# H-bro_gear.net
KiCad netlist of a schematic drawn in EAGLE
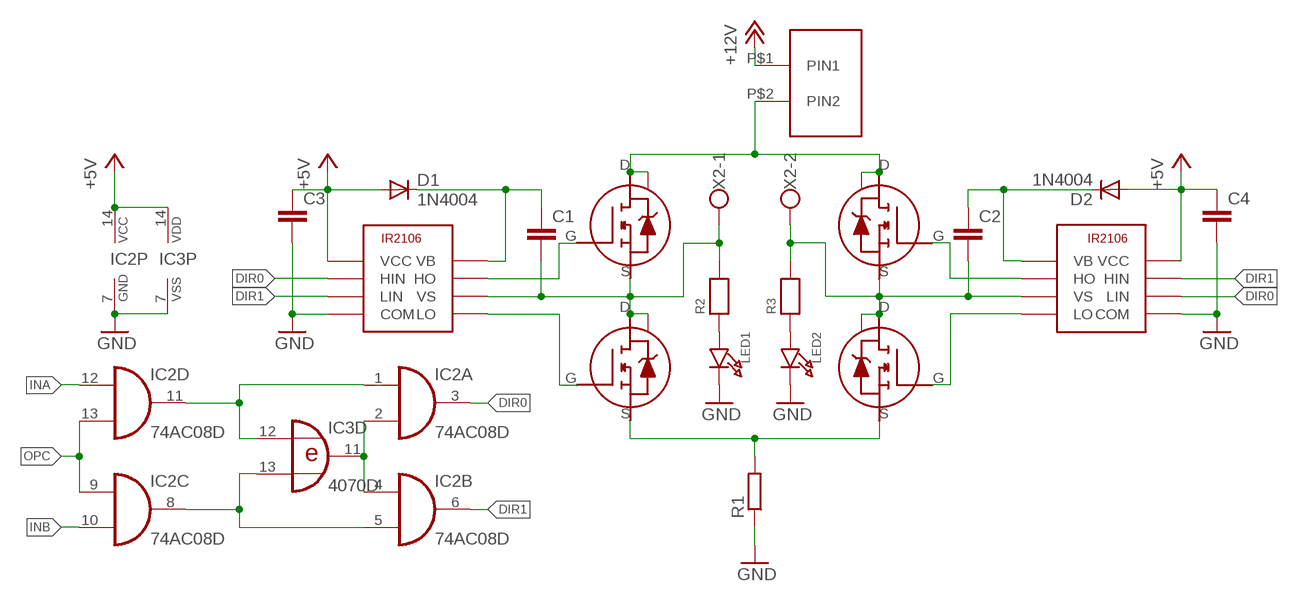
[diagram p0: schematic, sheet 1]

(export (version "E")
  (design (tool "Eeschema 10.0.6"))
  (components
    (comp (ref "C1")
      (value "C-EU050-025X075")
      (footprint "eagle-import:C050-025X075")
      (libsource (lib "eagle-import") (part "C-EU050-025X075"))
    )
    (comp (ref "C2")
      (value "C-EU050-025X075")
      (footprint "eagle-import:C050-025X075")
      (libsource (lib "eagle-import") (part "C-EU050-025X075"))
    )
    (comp (ref "C3")
      (value "C-EU050-025X075")
      (footprint "eagle-import:C050-025X075")
      (libsource (lib "eagle-import") (part "C-EU050-025X075"))
    )
    (comp (ref "C4")
      (value "C-EU050-025X075")
      (footprint "eagle-import:C050-025X075")
      (libsource (lib "eagle-import") (part "C-EU050-025X075"))
    )
    (comp (ref "D1")
      (value "1N4004")
      (footprint "eagle-import:DO41-10")
      (libsource (lib "eagle-import") (part "1N4004"))
    )
    (comp (ref "D2")
      (value "1N4004")
      (footprint "eagle-import:DO41-10")
      (libsource (lib "eagle-import") (part "1N4004"))
    )
    (comp (ref "IC2")
      (value "74AC08D")
      (footprint "eagle-import:SO14")
      (libsource (lib "eagle-import") (part "7408DAC"))
    )
    (comp (ref "IC3")
      (value "4070D")
      (footprint "eagle-import:SO14")
      (libsource (lib "eagle-import") (part "4070D"))
    )
    (comp (ref "LED1")
      (value "LED1206")
      (footprint "eagle-import:CHIPLED_1206")
      (libsource (lib "eagle-import") (part "LED1206"))
    )
    (comp (ref "LED2")
      (value "LED1206")
      (footprint "eagle-import:CHIPLED_1206")
      (libsource (lib "eagle-import") (part "LED1206"))
    )
    (comp (ref "R1")
      (value "R-EU_0309/12")
      (footprint "eagle-import:0309_12")
      (libsource (lib "eagle-import") (part "R-EU_0309/12"))
    )
    (comp (ref "R2")
      (value "RESISTOR_0603")
      (footprint "eagle-import:_0603")
      (libsource (lib "eagle-import") (part "RESISTOR_0603"))
    )
    (comp (ref "R3")
      (value "RESISTOR_0603")
      (footprint "eagle-import:_0603")
      (libsource (lib "eagle-import") (part "RESISTOR_0603"))
    )
    (comp (ref "U$1")
      (value "IR2106")
      (footprint "eagle-import:IR2106")
      (libsource (lib "eagle-import") (part "IR2106"))
    )
    (comp (ref "U$2")
      (value "IR2106")
      (footprint "eagle-import:IR2106")
      (libsource (lib "eagle-import") (part "IR2106"))
    )
    (comp (ref "U$3")
      (value "STU95N5")
      (footprint "eagle-import:STU95N5")
      (libsource (lib "eagle-import") (part "STU95N5"))
    )
    (comp (ref "U$4")
      (value "STU95N5")
      (footprint "eagle-import:STU95N5")
      (libsource (lib "eagle-import") (part "STU95N5"))
    )
    (comp (ref "U$5")
      (value "STU95N5")
      (footprint "eagle-import:STU95N5")
      (libsource (lib "eagle-import") (part "STU95N5"))
    )
    (comp (ref "U$6")
      (value "STU95N5")
      (footprint "eagle-import:STU95N5")
      (libsource (lib "eagle-import") (part "STU95N5"))
    )
    (comp (ref "U$7")
      (value "LITTE_FUSE")
      (footprint "eagle-import:LITTE_FUSE_PAC")
      (libsource (lib "eagle-import") (part "LITTE_FUSE"))
    )
    (comp (ref "X2")
      (value "W237-102")
      (footprint "eagle-import:W237-102")
      (fields (field (name "MPN") "237-102"))
      (libsource (lib "eagle-import") (part "W237-102"))
    )
  )
  (nets
    (net (code "1") (name "+5V") (class "Default")
      (node (ref "C3") (pin "1") (pinfunction "1_1") (pintype "passive"))
      (node (ref "C4") (pin "1") (pinfunction "1_1") (pintype "passive"))
      (node (ref "D1") (pin "A") (pinfunction "A_A") (pintype "passive"))
      (node (ref "D2") (pin "A") (pinfunction "A_A") (pintype "passive"))
      (node (ref "IC2") (pin "14") (pinfunction "VCC_14") (pintype "power_in"))
      (node (ref "IC3") (pin "14") (pinfunction "VDD_14") (pintype "power_in"))
      (node (ref "U$1") (pin "VCC") (pinfunction "VCC_VCC") (pintype "bidirectional"))
      (node (ref "U$2") (pin "VCC") (pinfunction "VCC_VCC") (pintype "bidirectional"))
    )
    (net (code "2") (name "+12V") (class "Default")
      (node (ref "U$7") (pin "P$1") (pinfunction "PIN1_P$1") (pintype "bidirectional"))
    )
    (net (code "3") (name "DIR0") (class "Default")
      (node (ref "IC2") (pin "3") (pinfunction "O_3") (pintype "output"))
      (node (ref "U$1") (pin "HIN") (pinfunction "HIN_HIN") (pintype "bidirectional"))
      (node (ref "U$2") (pin "LIN") (pinfunction "LIN_LIN") (pintype "bidirectional"))
    )
    (net (code "4") (name "DIR1") (class "Default")
      (node (ref "IC2") (pin "6") (pinfunction "O_6") (pintype "output"))
      (node (ref "U$1") (pin "LIN") (pinfunction "LIN_LIN") (pintype "bidirectional"))
      (node (ref "U$2") (pin "HIN") (pinfunction "HIN_HIN") (pintype "bidirectional"))
    )
    (net (code "5") (name "GND") (class "Default")
      (node (ref "C3") (pin "2") (pinfunction "2_2") (pintype "passive"))
      (node (ref "C4") (pin "2") (pinfunction "2_2") (pintype "passive"))
      (node (ref "IC2") (pin "7") (pinfunction "GND_7") (pintype "power_in"))
      (node (ref "IC3") (pin "7") (pinfunction "VSS_7") (pintype "power_in"))
      (node (ref "LED1") (pin "C") (pinfunction "C_C") (pintype "passive"))
      (node (ref "LED2") (pin "C") (pinfunction "C_C") (pintype "passive"))
      (node (ref "R1") (pin "1") (pinfunction "1_1") (pintype "passive"))
      (node (ref "U$1") (pin "COM") (pinfunction "COM_COM") (pintype "bidirectional"))
      (node (ref "U$2") (pin "COM") (pinfunction "COM_COM") (pintype "bidirectional"))
    )
    (net (code "6") (name "INA") (class "Default")
      (node (ref "IC2") (pin "12") (pinfunction "I0_12") (pintype "input"))
    )
    (net (code "7") (name "INB") (class "Default")
      (node (ref "IC2") (pin "10") (pinfunction "I1_10") (pintype "input"))
    )
    (net (code "8") (name "Net-(C1-Pad1)") (class "Default")
      (node (ref "C1") (pin "1") (pinfunction "1_1") (pintype "passive"))
      (node (ref "D1") (pin "C") (pinfunction "C_C") (pintype "passive"))
      (node (ref "U$1") (pin "VB") (pinfunction "VB_VB") (pintype "bidirectional"))
    )
    (net (code "9") (name "Net-(C2-Pad1)") (class "Default")
      (node (ref "C2") (pin "1") (pinfunction "1_1") (pintype "passive"))
      (node (ref "D2") (pin "C") (pinfunction "C_C") (pintype "passive"))
      (node (ref "U$2") (pin "VB") (pinfunction "VB_VB") (pintype "bidirectional"))
    )
    (net (code "10") (name "Net-(IC2A-I0)") (class "Default")
      (node (ref "IC2") (pin "1") (pinfunction "I0_1") (pintype "input"))
      (node (ref "IC2") (pin "11") (pinfunction "O_11") (pintype "output"))
      (node (ref "IC3") (pin "12") (pinfunction "I0_12") (pintype "input"))
    )
    (net (code "11") (name "Net-(IC2A-I1)") (class "Default")
      (node (ref "IC2") (pin "2") (pinfunction "I1_2") (pintype "input"))
      (node (ref "IC2") (pin "4") (pinfunction "I0_4") (pintype "input"))
      (node (ref "IC3") (pin "11") (pinfunction "O_11") (pintype "output"))
    )
    (net (code "12") (name "Net-(IC2B-I1)") (class "Default")
      (node (ref "IC2") (pin "5") (pinfunction "I1_5") (pintype "input"))
      (node (ref "IC2") (pin "8") (pinfunction "O_8") (pintype "output"))
      (node (ref "IC3") (pin "13") (pinfunction "I1_13") (pintype "input"))
    )
    (net (code "13") (name "Net-(LED1-PadA)") (class "Default")
      (node (ref "LED1") (pin "A") (pinfunction "A_A") (pintype "passive"))
      (node (ref "R2") (pin "1") (pinfunction "1_1") (pintype "passive"))
    )
    (net (code "14") (name "Net-(LED2-PadA)") (class "Default")
      (node (ref "LED2") (pin "A") (pinfunction "A_A") (pintype "passive"))
      (node (ref "R3") (pin "1") (pinfunction "1_1") (pintype "passive"))
    )
    (net (code "15") (name "Net-(R1-Pad2)") (class "Default")
      (node (ref "R1") (pin "2") (pinfunction "2_2") (pintype "passive"))
      (node (ref "U$4") (pin "S") (pinfunction "S_S") (pintype "bidirectional"))
      (node (ref "U$5") (pin "S") (pinfunction "S_S") (pintype "bidirectional"))
    )
    (net (code "16") (name "Net-(U$1-PadHO)") (class "Default")
      (node (ref "U$1") (pin "HO") (pinfunction "HO_HO") (pintype "bidirectional"))
      (node (ref "U$3") (pin "G") (pinfunction "G_G") (pintype "bidirectional"))
    )
    (net (code "17") (name "Net-(U$1-PadLO)") (class "Default")
      (node (ref "U$1") (pin "LO") (pinfunction "LO_LO") (pintype "bidirectional"))
      (node (ref "U$4") (pin "G") (pinfunction "G_G") (pintype "bidirectional"))
    )
    (net (code "18") (name "Net-(U$2-PadHO)") (class "Default")
      (node (ref "U$2") (pin "HO") (pinfunction "HO_HO") (pintype "bidirectional"))
      (node (ref "U$6") (pin "G") (pinfunction "G_G") (pintype "bidirectional"))
    )
    (net (code "19") (name "Net-(U$2-PadLO)") (class "Default")
      (node (ref "U$2") (pin "LO") (pinfunction "LO_LO") (pintype "bidirectional"))
      (node (ref "U$5") (pin "G") (pinfunction "G_G") (pintype "bidirectional"))
    )
    (net (code "20") (name "Net-(U$7-PIN2)") (class "Default")
      (node (ref "U$3") (pin "D") (pinfunction "D_D") (pintype "bidirectional"))
      (node (ref "U$3") (pin "TAB") (pinfunction "TAB_TAB") (pintype "bidirectional"))
      (node (ref "U$6") (pin "D") (pinfunction "D_D") (pintype "bidirectional"))
      (node (ref "U$6") (pin "TAB") (pinfunction "TAB_TAB") (pintype "bidirectional"))
      (node (ref "U$7") (pin "P$2") (pinfunction "PIN2_P$2") (pintype "bidirectional"))
    )
    (net (code "21") (name "Net-(X2A-KL)") (class "Default")
      (node (ref "C1") (pin "2") (pinfunction "2_2") (pintype "passive"))
      (node (ref "R2") (pin "2") (pinfunction "2_2") (pintype "passive"))
      (node (ref "U$1") (pin "VS") (pinfunction "VS_VS") (pintype "bidirectional"))
      (node (ref "U$3") (pin "S") (pinfunction "S_S") (pintype "bidirectional"))
      (node (ref "U$4") (pin "D") (pinfunction "D_D") (pintype "bidirectional"))
      (node (ref "U$4") (pin "TAB") (pinfunction "TAB_TAB") (pintype "bidirectional"))
      (node (ref "X2") (pin "1") (pinfunction "KL_1") (pintype "passive"))
    )
    (net (code "22") (name "Net-(X2B-KL)") (class "Default")
      (node (ref "C2") (pin "2") (pinfunction "2_2") (pintype "passive"))
      (node (ref "R3") (pin "2") (pinfunction "2_2") (pintype "passive"))
      (node (ref "U$2") (pin "VS") (pinfunction "VS_VS") (pintype "bidirectional"))
      (node (ref "U$5") (pin "D") (pinfunction "D_D") (pintype "bidirectional"))
      (node (ref "U$5") (pin "TAB") (pinfunction "TAB_TAB") (pintype "bidirectional"))
      (node (ref "U$6") (pin "S") (pinfunction "S_S") (pintype "bidirectional"))
      (node (ref "X2") (pin "2") (pinfunction "KL_2") (pintype "passive"))
    )
    (net (code "23") (name "OPC") (class "Default")
      (node (ref "IC2") (pin "13") (pinfunction "I1_13") (pintype "input"))
      (node (ref "IC2") (pin "9") (pinfunction "I0_9") (pintype "input"))
    )
  )
)
